# Control.net
KiCad netlist of a schematic drawn in EAGLE
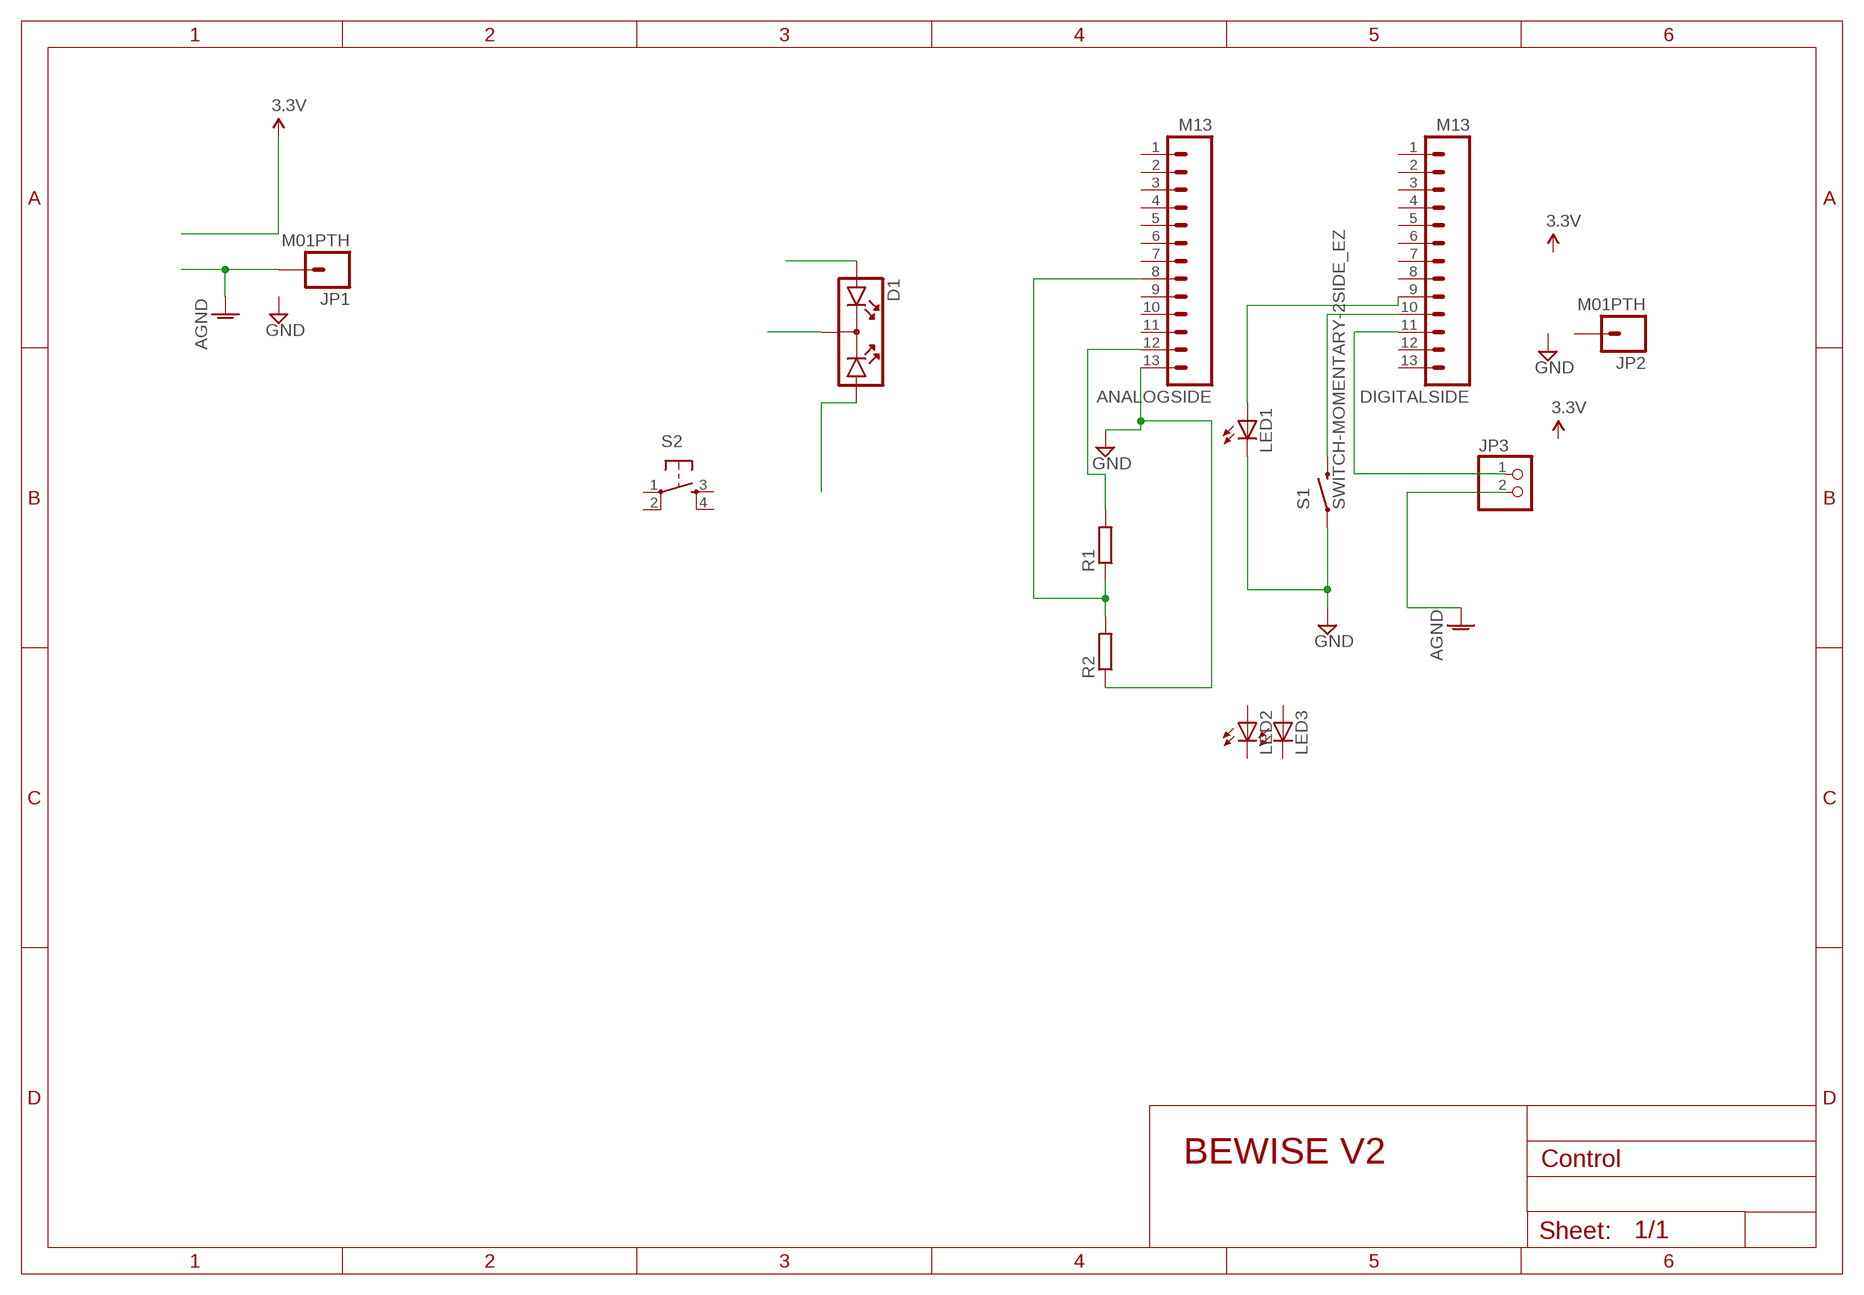
[diagram p0: schematic, sheet 1]

(export (version "E")
  (design (tool "Eeschema 10.0.6"))
  (components
    (comp (ref "ANALOGSIDE")
      (value "M13")
      (footprint "eagle-import:1X13")
      (libsource (lib "eagle-import") (part "M13"))
    )
    (comp (ref "D1")
      (value "DUOLED")
      (footprint "eagle-import:DUOLED")
      (libsource (lib "eagle-import") (part "DUOLED"))
    )
    (comp (ref "DIGITALSIDE")
      (value "M13")
      (footprint "eagle-import:1X13")
      (libsource (lib "eagle-import") (part "M13"))
    )
    (comp (ref "JP1")
      (value "M01PTH")
      (footprint "eagle-import:1X01")
      (libsource (lib "eagle-import") (part "M01PTH"))
    )
    (comp (ref "JP2")
      (value "M01PTH")
      (footprint "eagle-import:1X01")
      (libsource (lib "eagle-import") (part "M01PTH"))
    )
    (comp (ref "JP3")
      (value "PINHD-1X2")
      (footprint "eagle-import:1X02")
      (libsource (lib "eagle-import") (part "PINHD-1X2"))
    )
    (comp (ref "LED1")
      (value "LED3MM")
      (footprint "eagle-import:LED3MM")
      (libsource (lib "eagle-import") (part "LED3MM"))
    )
    (comp (ref "LED2")
      (value "LED3MM")
      (footprint "eagle-import:LED3MM")
      (libsource (lib "eagle-import") (part "LED3MM"))
    )
    (comp (ref "LED3")
      (value "LED3MM")
      (footprint "eagle-import:LED3MM")
      (libsource (lib "eagle-import") (part "LED3MM"))
    )
    (comp (ref "R1")
      (value "R-EU_0204/7")
      (footprint "eagle-import:0204_7")
      (libsource (lib "eagle-import") (part "R-EU_0204/7"))
    )
    (comp (ref "R2")
      (value "R-EU_0204/7")
      (footprint "eagle-import:0204_7")
      (libsource (lib "eagle-import") (part "R-EU_0204/7"))
    )
    (comp (ref "S1")
      (value "SWITCH-MOMENTARY-2SIDE_EZ")
      (footprint "eagle-import:TACTILE-PTH-SIDEEZ")
      (libsource (lib "eagle-import") (part "SWITCH-MOMENTARY-2SIDE_EZ"))
    )
    (comp (ref "S2")
      (value "TAC_SWITCHPTH")
      (footprint "eagle-import:TACTILE-PTH")
      (libsource (lib "eagle-import") (part "TAC_SWITCHPTH"))
    )
  )
  (nets
    (net (code "2") (name "AGND") (class "Default")
      (node (ref "JP1") (pin "1") (pinfunction "1_1") (pintype "passive"))
      (node (ref "JP3") (pin "2") (pinfunction "2_2") (pintype "passive"))
    )
    (net (code "3") (name "GND") (class "Default")
      (node (ref "ANALOGSIDE") (pin "13") (pinfunction "13_13") (pintype "passive"))
      (node (ref "LED1") (pin "K") (pinfunction "C_K") (pintype "passive"))
      (node (ref "R2") (pin "1") (pinfunction "1_1") (pintype "passive"))
      (node (ref "S1") (pin "1") (pinfunction "1_1") (pintype "passive"))
    )
    (net (code "4") (name "Net-(ANALOGSIDE-Pad8)") (class "Default")
      (node (ref "ANALOGSIDE") (pin "8") (pinfunction "8_8") (pintype "passive"))
      (node (ref "R1") (pin "1") (pinfunction "1_1") (pintype "passive"))
      (node (ref "R2") (pin "2") (pinfunction "2_2") (pintype "passive"))
    )
    (net (code "5") (name "Net-(ANALOGSIDE-Pad12)") (class "Default")
      (node (ref "ANALOGSIDE") (pin "12") (pinfunction "12_12") (pintype "passive"))
      (node (ref "R1") (pin "2") (pinfunction "2_2") (pintype "passive"))
    )
    (net (code "6") (name "Net-(DIGITALSIDE-Pad9)") (class "Default")
      (node (ref "DIGITALSIDE") (pin "9") (pinfunction "9_9") (pintype "passive"))
      (node (ref "LED1") (pin "A") (pinfunction "A_A") (pintype "passive"))
    )
    (net (code "7") (name "Net-(DIGITALSIDE-Pad10)") (class "Default")
      (node (ref "DIGITALSIDE") (pin "10") (pinfunction "10_10") (pintype "passive"))
      (node (ref "S1") (pin "2") (pinfunction "2_2") (pintype "passive"))
    )
    (net (code "8") (name "Net-(DIGITALSIDE-Pad11)") (class "Default")
      (node (ref "DIGITALSIDE") (pin "11") (pinfunction "11_11") (pintype "passive"))
      (node (ref "JP3") (pin "1") (pinfunction "1_1") (pintype "passive"))
    )
    (net (code "9") (name "unconnected-(ANALOGSIDE-Pad1)") (class "Default")
      (node (ref "ANALOGSIDE") (pin "1") (pinfunction "1_1") (pintype "passive"))
    )
    (net (code "10") (name "unconnected-(ANALOGSIDE-Pad2)") (class "Default")
      (node (ref "ANALOGSIDE") (pin "2") (pinfunction "2_2") (pintype "passive"))
    )
    (net (code "11") (name "unconnected-(ANALOGSIDE-Pad3)") (class "Default")
      (node (ref "ANALOGSIDE") (pin "3") (pinfunction "3_3") (pintype "passive"))
    )
    (net (code "12") (name "unconnected-(ANALOGSIDE-Pad4)") (class "Default")
      (node (ref "ANALOGSIDE") (pin "4") (pinfunction "4_4") (pintype "passive"))
    )
    (net (code "13") (name "unconnected-(ANALOGSIDE-Pad5)") (class "Default")
      (node (ref "ANALOGSIDE") (pin "5") (pinfunction "5_5") (pintype "passive"))
    )
    (net (code "14") (name "unconnected-(ANALOGSIDE-Pad6)") (class "Default")
      (node (ref "ANALOGSIDE") (pin "6") (pinfunction "6_6") (pintype "passive"))
    )
    (net (code "15") (name "unconnected-(ANALOGSIDE-Pad7)") (class "Default")
      (node (ref "ANALOGSIDE") (pin "7") (pinfunction "7_7") (pintype "passive"))
    )
    (net (code "16") (name "unconnected-(ANALOGSIDE-Pad9)") (class "Default")
      (node (ref "ANALOGSIDE") (pin "9") (pinfunction "9_9") (pintype "passive"))
    )
    (net (code "17") (name "unconnected-(ANALOGSIDE-Pad10)") (class "Default")
      (node (ref "ANALOGSIDE") (pin "10") (pinfunction "10_10") (pintype "passive"))
    )
    (net (code "18") (name "unconnected-(ANALOGSIDE-Pad11)") (class "Default")
      (node (ref "ANALOGSIDE") (pin "11") (pinfunction "11_11") (pintype "passive"))
    )
    (net (code "19") (name "unconnected-(D1-PadA1)") (class "Default")
      (node (ref "D1") (pin "A1") (pinfunction "A1_A1") (pintype "passive"))
    )
    (net (code "20") (name "unconnected-(D1-PadA2)") (class "Default")
      (node (ref "D1") (pin "A2") (pinfunction "A2_A2") (pintype "passive"))
    )
    (net (code "21") (name "unconnected-(D1-PadK)") (class "Default")
      (node (ref "D1") (pin "K") (pinfunction "K_K") (pintype "passive"))
    )
    (net (code "22") (name "unconnected-(DIGITALSIDE-Pad1)") (class "Default")
      (node (ref "DIGITALSIDE") (pin "1") (pinfunction "1_1") (pintype "passive"))
    )
    (net (code "23") (name "unconnected-(DIGITALSIDE-Pad2)") (class "Default")
      (node (ref "DIGITALSIDE") (pin "2") (pinfunction "2_2") (pintype "passive"))
    )
    (net (code "24") (name "unconnected-(DIGITALSIDE-Pad3)") (class "Default")
      (node (ref "DIGITALSIDE") (pin "3") (pinfunction "3_3") (pintype "passive"))
    )
    (net (code "25") (name "unconnected-(DIGITALSIDE-Pad4)") (class "Default")
      (node (ref "DIGITALSIDE") (pin "4") (pinfunction "4_4") (pintype "passive"))
    )
    (net (code "26") (name "unconnected-(DIGITALSIDE-Pad5)") (class "Default")
      (node (ref "DIGITALSIDE") (pin "5") (pinfunction "5_5") (pintype "passive"))
    )
    (net (code "27") (name "unconnected-(DIGITALSIDE-Pad6)") (class "Default")
      (node (ref "DIGITALSIDE") (pin "6") (pinfunction "6_6") (pintype "passive"))
    )
    (net (code "28") (name "unconnected-(DIGITALSIDE-Pad7)") (class "Default")
      (node (ref "DIGITALSIDE") (pin "7") (pinfunction "7_7") (pintype "passive"))
    )
    (net (code "29") (name "unconnected-(DIGITALSIDE-Pad8)") (class "Default")
      (node (ref "DIGITALSIDE") (pin "8") (pinfunction "8_8") (pintype "passive"))
    )
    (net (code "30") (name "unconnected-(DIGITALSIDE-Pad12)") (class "Default")
      (node (ref "DIGITALSIDE") (pin "12") (pinfunction "12_12") (pintype "passive"))
    )
    (net (code "31") (name "unconnected-(DIGITALSIDE-Pad13)") (class "Default")
      (node (ref "DIGITALSIDE") (pin "13") (pinfunction "13_13") (pintype "passive"))
    )
    (net (code "32") (name "unconnected-(JP2-Pad1)") (class "Default")
      (node (ref "JP2") (pin "1") (pinfunction "1_1") (pintype "passive"))
    )
    (net (code "33") (name "unconnected-(LED2-C-PadK)") (class "Default")
      (node (ref "LED2") (pin "K") (pinfunction "C_K") (pintype "passive"))
    )
    (net (code "34") (name "unconnected-(LED2-PadA)") (class "Default")
      (node (ref "LED2") (pin "A") (pinfunction "A_A") (pintype "passive"))
    )
    (net (code "35") (name "unconnected-(LED3-C-PadK)") (class "Default")
      (node (ref "LED3") (pin "K") (pinfunction "C_K") (pintype "passive"))
    )
    (net (code "36") (name "unconnected-(LED3-PadA)") (class "Default")
      (node (ref "LED3") (pin "A") (pinfunction "A_A") (pintype "passive"))
    )
    (net (code "37") (name "unconnected-(S2-Pad1)") (class "Default")
      (node (ref "S2") (pin "1") (pinfunction "1_1") (pintype "passive"))
    )
    (net (code "38") (name "unconnected-(S2-Pad2)") (class "Default")
      (node (ref "S2") (pin "2") (pinfunction "2_2") (pintype "passive"))
    )
    (net (code "39") (name "unconnected-(S2-Pad3)") (class "Default")
      (node (ref "S2") (pin "3") (pinfunction "3_3") (pintype "passive"))
    )
    (net (code "40") (name "unconnected-(S2-Pad4)") (class "Default")
      (node (ref "S2") (pin "4") (pinfunction "4_4") (pintype "passive"))
    )
  )
)
